# 5V_STEPDOWN.net
KiCad netlist of a schematic drawn in EAGLE
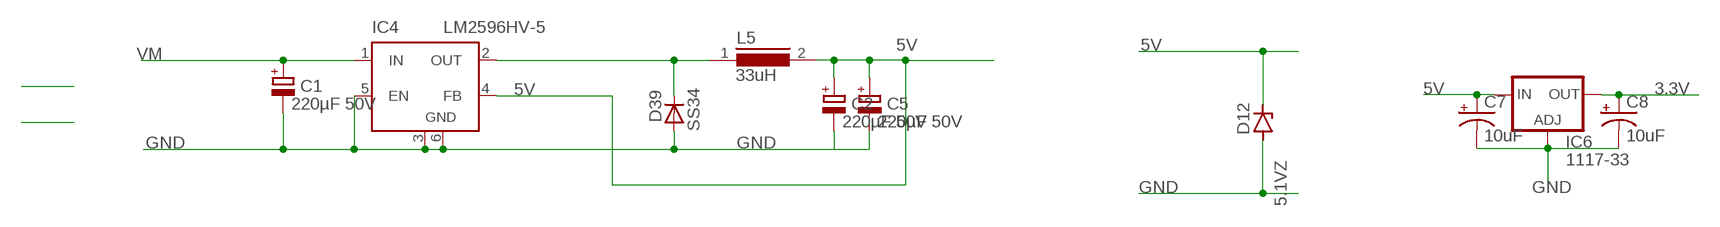
[diagram p0: schematic, sheet 1]

(export (version "E")
  (design (tool "Eeschema 10.0.6"))
  (components
    (comp (ref "C1")
      (value "220µF 50V")
      (footprint "eagle-import:E3,5-8")
      (libsource (lib "eagle-import") (part "CPOL-EUE3.5-8"))
    )
    (comp (ref "C2")
      (value "220µF 50V")
      (footprint "eagle-import:E3,5-8")
      (libsource (lib "eagle-import") (part "CPOL-EUE3.5-8"))
    )
    (comp (ref "C5")
      (value "220µF 50V")
      (footprint "eagle-import:E3,5-8")
      (libsource (lib "eagle-import") (part "CPOL-EUE3.5-8"))
    )
    (comp (ref "C7")
      (value "10uF")
      (footprint "eagle-import:CPOL-RADIAL-10UF-25V")
      (libsource (lib "eagle-import") (part "CAP_POLPTH2"))
    )
    (comp (ref "C8")
      (value "10uF")
      (footprint "eagle-import:CPOL-RADIAL-10UF-25V")
      (libsource (lib "eagle-import") (part "CAP_POLPTH2"))
    )
    (comp (ref "D12")
      (value "5.1VZ")
      (footprint "eagle-import:SMB")
      (libsource (lib "eagle-import") (part "ZENER-DIODESMB"))
    )
    (comp (ref "D39")
      (value "SS34")
      (footprint "eagle-import:SOD87")
      (libsource (lib "eagle-import") (part "D-SOD-87"))
    )
    (comp (ref "IC4")
      (value "LM2596HV-5")
      (footprint "eagle-import:TO263-5")
      (libsource (lib "eagle-import") (part "LM2596S"))
    )
    (comp (ref "IC6")
      (value "1117-33")
      (footprint "eagle-import:SOT223")
      (libsource (lib "eagle-import") (part "LD117A?S33TR"))
    )
    (comp (ref "L5")
      (value "33uH")
      (footprint "eagle-import:DR127")
      (libsource (lib "eagle-import") (part "DR127"))
    )
  )
  (nets
    (net (code "1") (name "/3.3V") (class "Default")
      (node (ref "C8") (pin "1") (pinfunction "+_1") (pintype "passive"))
      (node (ref "IC6") (pin "4") (pinfunction "OUT_4") (pintype "passive"))
    )
    (net (code "2") (name "/5V") (class "Default")
      (node (ref "C2") (pin "+") (pinfunction "+_+") (pintype "passive"))
      (node (ref "C5") (pin "+") (pinfunction "+_+") (pintype "passive"))
      (node (ref "C7") (pin "1") (pinfunction "+_1") (pintype "passive"))
      (node (ref "D12") (pin "C") (pinfunction "C_C") (pintype "passive"))
      (node (ref "IC4") (pin "4") (pinfunction "FB_4") (pintype "input"))
      (node (ref "IC6") (pin "3") (pinfunction "IN_3") (pintype "input"))
      (node (ref "L5") (pin "2") (pinfunction "2_2") (pintype "passive"))
    )
    (net (code "3") (name "/GND") (class "Default")
      (node (ref "C1") (pin "-") (pinfunction "-_-") (pintype "passive"))
      (node (ref "C2") (pin "-") (pinfunction "-_-") (pintype "passive"))
      (node (ref "C5") (pin "-") (pinfunction "-_-") (pintype "passive"))
      (node (ref "C7") (pin "2") (pinfunction "-_2") (pintype "passive"))
      (node (ref "C8") (pin "2") (pinfunction "-_2") (pintype "passive"))
      (node (ref "D12") (pin "A") (pinfunction "A_A") (pintype "passive"))
      (node (ref "D39") (pin "2") (pinfunction "A_2") (pintype "passive"))
      (node (ref "IC4") (pin "3") (pinfunction "GND_3") (pintype "power_in"))
      (node (ref "IC4") (pin "5") (pinfunction "EN_5") (pintype "input"))
      (node (ref "IC4") (pin "6") (pinfunction "GND_6") (pintype "power_in"))
      (node (ref "IC6") (pin "1") (pinfunction "ADJ_1") (pintype "input"))
    )
    (net (code "4") (name "/VM") (class "Default")
      (node (ref "C1") (pin "+") (pinfunction "+_+") (pintype "passive"))
      (node (ref "IC4") (pin "1") (pinfunction "IN_1") (pintype "input"))
    )
    (net (code "5") (name "Net-(D39-C)") (class "Default")
      (node (ref "D39") (pin "1") (pinfunction "C_1") (pintype "passive"))
      (node (ref "IC4") (pin "2") (pinfunction "OUT_2") (pintype "output"))
      (node (ref "L5") (pin "1") (pinfunction "1_1") (pintype "passive"))
    )
  )
)
